# esp32buscam_01.net
KiCad netlist of a schematic drawn in EAGLE
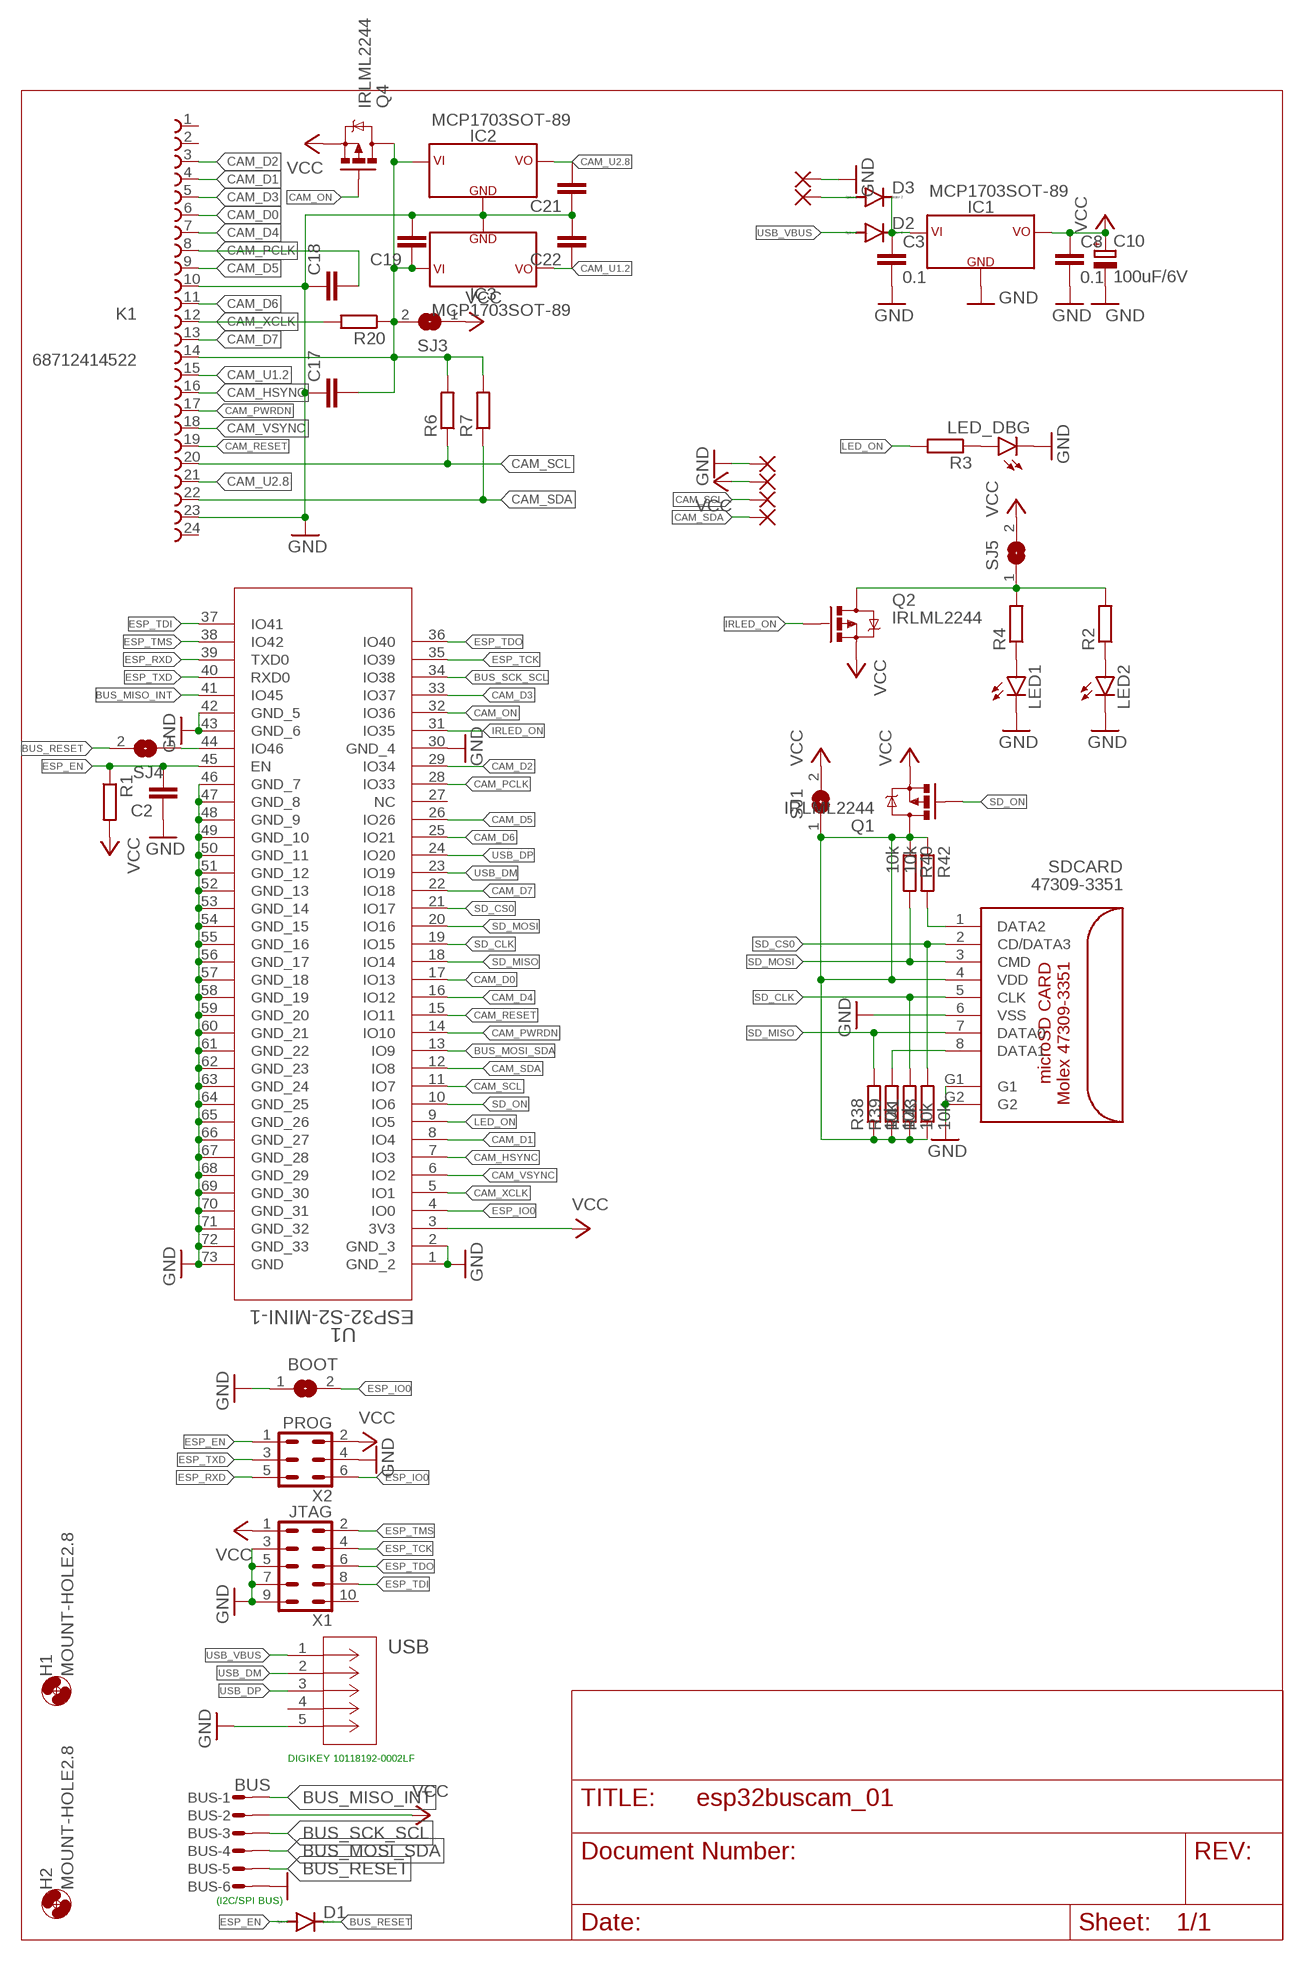
[diagram p0: schematic, sheet 1]

(export (version "E")
  (design (tool "Eeschema 10.0.6"))
  (components
    (comp (ref "BOOT")
      (value "SJ")
      (footprint "eagle-import:SJ")
      (libsource (lib "eagle-import") (part "SJ"))
    )
    (comp (ref "BUS")
      (value "BUS")
      (footprint "eagle-import:MICROMATCH-6SMD")
      (libsource (lib "eagle-import") (part "MICROMATCH-6SMD"))
    )
    (comp (ref "C2")
      (value "C-EUC0603")
      (footprint "eagle-import:C0603")
      (libsource (lib "eagle-import") (part "rcl_334_C-EUC0603"))
    )
    (comp (ref "C3")
      (value "0.1")
      (footprint "eagle-import:C0805")
      (libsource (lib "eagle-import") (part "C-EUC0805"))
    )
    (comp (ref "C8")
      (value "0.1")
      (footprint "eagle-import:C0805")
      (libsource (lib "eagle-import") (part "C-EUC0805"))
    )
    (comp (ref "C10")
      (value "100uF/6V")
      (footprint "eagle-import:B_3528-21R")
      (libsource (lib "eagle-import") (part "CPOL-EUB/3528-21R"))
    )
    (comp (ref "C17")
      (value "C-EUC0603")
      (footprint "eagle-import:C0603")
      (libsource (lib "eagle-import") (part "rcl_334_C-EUC0603"))
    )
    (comp (ref "C18")
      (value "C-EUC0603")
      (footprint "eagle-import:C0603")
      (libsource (lib "eagle-import") (part "rcl_334_C-EUC0603"))
    )
    (comp (ref "C19")
      (value "C-EUC0603")
      (footprint "eagle-import:C0603")
      (libsource (lib "eagle-import") (part "rcl_334_C-EUC0603"))
    )
    (comp (ref "C21")
      (value "C-EUC0603")
      (footprint "eagle-import:C0603")
      (libsource (lib "eagle-import") (part "rcl_334_C-EUC0603"))
    )
    (comp (ref "C22")
      (value "C-EUC0603")
      (footprint "eagle-import:C0603")
      (libsource (lib "eagle-import") (part "rcl_334_C-EUC0603"))
    )
    (comp (ref "D1")
      (value "DIODE-MINIMELF")
      (footprint "eagle-import:MINIMELF")
      (libsource (lib "eagle-import") (part "DIODE-MINIMELF"))
    )
    (comp (ref "D2")
      (value "DIODE-MINIMELF")
      (footprint "eagle-import:MINIMELF")
      (libsource (lib "eagle-import") (part "DIODE-MINIMELF"))
    )
    (comp (ref "D3")
      (value "DIODE-MINIMELF")
      (footprint "eagle-import:MINIMELF")
      (libsource (lib "eagle-import") (part "DIODE-MINIMELF"))
    )
    (comp (ref "H1")
      (value "MOUNT-HOLE2.8")
      (footprint "eagle-import:2,8")
      (libsource (lib "eagle-import") (part "MOUNT-HOLE2.8"))
    )
    (comp (ref "H2")
      (value "MOUNT-HOLE2.8")
      (footprint "eagle-import:2,8")
      (libsource (lib "eagle-import") (part "MOUNT-HOLE2.8"))
    )
    (comp (ref "IC1")
      (value "MCP1703SOT-89")
      (footprint "eagle-import:SOT89")
      (libsource (lib "eagle-import") (part "MCP1703SOT-89"))
    )
    (comp (ref "IC2")
      (value "MCP1703SOT-89")
      (footprint "eagle-import:SOT89")
      (libsource (lib "eagle-import") (part "MCP1703SOT-89"))
    )
    (comp (ref "IC3")
      (value "MCP1703SOT-89")
      (footprint "eagle-import:SOT89")
      (libsource (lib "eagle-import") (part "MCP1703SOT-89"))
    )
    (comp (ref "K1")
      (value "68712414522")
      (footprint "eagle-import:68712414522")
      (libsource (lib "eagle-import") (part "68712414522"))
    )
    (comp (ref "LED1")
      (value "LED5MM")
      (footprint "eagle-import:LED5MM")
      (libsource (lib "eagle-import") (part "LED5MM"))
    )
    (comp (ref "LED2")
      (value "LED5MM")
      (footprint "eagle-import:LED5MM")
      (libsource (lib "eagle-import") (part "LED5MM"))
    )
    (comp (ref "LED_DBG")
      (value "G")
      (footprint "eagle-import:CHIPLED_0805")
      (libsource (lib "eagle-import") (part "LEDCHIPLED_0805"))
    )
    (comp (ref "PAD1")
      (value "1,6/0,9")
      (footprint "eagle-import:1,6_0,9")
      (libsource (lib "eagle-import") (part "1,6/0,9"))
    )
    (comp (ref "PAD2")
      (value "1,6/0,9")
      (footprint "eagle-import:1,6_0,9")
      (libsource (lib "eagle-import") (part "1,6/0,9"))
    )
    (comp (ref "PAD3")
      (value "1,6/0,9")
      (footprint "eagle-import:1,6_0,9")
      (libsource (lib "eagle-import") (part "1,6/0,9"))
    )
    (comp (ref "PAD4")
      (value "1,6/0,9")
      (footprint "eagle-import:1,6_0,9")
      (libsource (lib "eagle-import") (part "1,6/0,9"))
    )
    (comp (ref "PAD5")
      (value "1,6/0,9")
      (footprint "eagle-import:1,6_0,9")
      (libsource (lib "eagle-import") (part "1,6/0,9"))
    )
    (comp (ref "PAD6")
      (value "1,6/0,9")
      (footprint "eagle-import:1,6_0,9")
      (libsource (lib "eagle-import") (part "1,6/0,9"))
    )
    (comp (ref "Q1")
      (value "IRLML2244")
      (footprint "eagle-import:SOT23-3")
      (libsource (lib "eagle-import") (part "MOSFET-PCHANNELIRLML2244"))
    )
    (comp (ref "Q2")
      (value "IRLML2244")
      (footprint "eagle-import:SOT23-3")
      (libsource (lib "eagle-import") (part "MOSFET-PCHANNELIRLML2244"))
    )
    (comp (ref "Q4")
      (value "IRLML2244")
      (footprint "eagle-import:SOT23-3")
      (libsource (lib "eagle-import") (part "MOSFET-PCHANNELIRLML2244"))
    )
    (comp (ref "R1")
      (value "R-EU_R0603")
      (footprint "eagle-import:R0603")
      (libsource (lib "eagle-import") (part "rcl_334_R-EU_R0603"))
    )
    (comp (ref "R2")
      (value "R-EU_R0402")
      (footprint "eagle-import:R0402")
      (libsource (lib "eagle-import") (part "rcl_334_R-EU_R0402"))
    )
    (comp (ref "R3")
      (value "R-EU_R0402")
      (footprint "eagle-import:R0402")
      (libsource (lib "eagle-import") (part "rcl_334_R-EU_R0402"))
    )
    (comp (ref "R4")
      (value "R-EU_R0402")
      (footprint "eagle-import:R0402")
      (libsource (lib "eagle-import") (part "rcl_334_R-EU_R0402"))
    )
    (comp (ref "R6")
      (value "R-EU_R0603")
      (footprint "eagle-import:R0603")
      (libsource (lib "eagle-import") (part "rcl_334_R-EU_R0603"))
    )
    (comp (ref "R7")
      (value "R-EU_R0603")
      (footprint "eagle-import:R0603")
      (libsource (lib "eagle-import") (part "rcl_334_R-EU_R0603"))
    )
    (comp (ref "R20")
      (value "R-EU_R0603")
      (footprint "eagle-import:R0603")
      (libsource (lib "eagle-import") (part "rcl_334_R-EU_R0603"))
    )
    (comp (ref "R38")
      (value "10k")
      (footprint "eagle-import:R0805")
      (libsource (lib "eagle-import") (part "R-EU_R0805"))
    )
    (comp (ref "R39")
      (value "10k")
      (footprint "eagle-import:R0805")
      (libsource (lib "eagle-import") (part "R-EU_R0805"))
    )
    (comp (ref "R40")
      (value "10k")
      (footprint "eagle-import:R0805")
      (libsource (lib "eagle-import") (part "R-EU_R0805"))
    )
    (comp (ref "R41")
      (value "10k")
      (footprint "eagle-import:R0805")
      (libsource (lib "eagle-import") (part "R-EU_R0805"))
    )
    (comp (ref "R42")
      (value "10k")
      (footprint "eagle-import:R0805")
      (libsource (lib "eagle-import") (part "R-EU_R0805"))
    )
    (comp (ref "R43")
      (value "10k")
      (footprint "eagle-import:R0805")
      (libsource (lib "eagle-import") (part "R-EU_R0805"))
    )
    (comp (ref "SDCARD")
      (value "47309-3351")
      (footprint "eagle-import:47309-3351")
      (libsource (lib "eagle-import") (part "47309-3351"))
    )
    (comp (ref "SJ1") (value "SJ") (footprint "eagle-import:SJ") (libsource (lib "eagle-import") (part "SJ")))
    (comp (ref "SJ3") (value "SJ") (footprint "eagle-import:SJ") (libsource (lib "eagle-import") (part "SJ")))
    (comp (ref "SJ4") (value "SJ") (footprint "eagle-import:SJ") (libsource (lib "eagle-import") (part "SJ")))
    (comp (ref "SJ5") (value "SJ") (footprint "eagle-import:SJ") (libsource (lib "eagle-import") (part "SJ")))
    (comp (ref "U1")
      (value "ESP32-S2-MINI-1")
      (footprint "eagle-import:QFN60_ESP32-S2-MINI-1_EXP")
      (fields (field (name "COPYRIGHT") "Copyright (C) 2018 Accelerated Designs. All rights reserved"))
      (libsource (lib "eagle-import") (part "ESP32-S2-MINI-1"))
    )
    (comp (ref "USB")
      (value "10118192-0002LF")
      (footprint "eagle-import:CONN_10118192-0002LF_AMP")
      (fields (field (name "COPYRIGHT") "Copyright (C) 2018 Accelerated Designs. All rights reserved"))
      (libsource (lib "eagle-import") (part "10118192-0002LF"))
    )
    (comp (ref "X1")
      (value "JTAG")
      (footprint "eagle-import:PHB_1MM27_2X05_SNS")
      (libsource (lib "eagle-import") (part "PHB_1MM27_2X05_SNS"))
    )
    (comp (ref "X2")
      (value "PROG")
      (footprint "eagle-import:PHB_1MM27_2X03_SNS")
      (libsource (lib "eagle-import") (part "PHB_1MM27_2X03_SNS"))
    )
  )
  (nets
    (net (code "1") (name "BUS_MISO_INT") (class "Default")
      (node (ref "BUS") (pin "1") (pinfunction "S_1") (pintype "passive"))
      (node (ref "U1") (pin "41") (pinfunction "IO45_41") (pintype "bidirectional"))
    )
    (net (code "2") (name "BUS_MOSI_SDA") (class "Default")
      (node (ref "BUS") (pin "4") (pinfunction "S_4") (pintype "passive"))
      (node (ref "U1") (pin "13") (pinfunction "IO9_13") (pintype "bidirectional"))
    )
    (net (code "3") (name "BUS_RESET") (class "Default")
      (node (ref "BUS") (pin "5") (pinfunction "S_5") (pintype "passive"))
      (node (ref "D1") (pin "C") (pinfunction "C_C") (pintype "passive"))
      (node (ref "SJ4") (pin "2") (pinfunction "2_2") (pintype "passive"))
    )
    (net (code "4") (name "BUS_SCK_SCL") (class "Default")
      (node (ref "BUS") (pin "3") (pinfunction "S_3") (pintype "passive"))
      (node (ref "U1") (pin "34") (pinfunction "IO38_34") (pintype "bidirectional"))
    )
    (net (code "5") (name "CAM_D0") (class "Default")
      (node (ref "K1") (pin "6") (pinfunction "6_6") (pintype "passive"))
      (node (ref "U1") (pin "17") (pinfunction "IO13_17") (pintype "bidirectional"))
    )
    (net (code "6") (name "CAM_D1") (class "Default")
      (node (ref "K1") (pin "4") (pinfunction "4_4") (pintype "passive"))
      (node (ref "U1") (pin "8") (pinfunction "IO4_8") (pintype "bidirectional"))
    )
    (net (code "7") (name "CAM_D2") (class "Default")
      (node (ref "K1") (pin "3") (pinfunction "3_3") (pintype "passive"))
      (node (ref "U1") (pin "29") (pinfunction "IO34_29") (pintype "bidirectional"))
    )
    (net (code "8") (name "CAM_D3") (class "Default")
      (node (ref "K1") (pin "5") (pinfunction "5_5") (pintype "passive"))
      (node (ref "U1") (pin "33") (pinfunction "IO37_33") (pintype "bidirectional"))
    )
    (net (code "9") (name "CAM_D4") (class "Default")
      (node (ref "K1") (pin "7") (pinfunction "7_7") (pintype "passive"))
      (node (ref "U1") (pin "16") (pinfunction "IO12_16") (pintype "bidirectional"))
    )
    (net (code "10") (name "CAM_D5") (class "Default")
      (node (ref "K1") (pin "9") (pinfunction "9_9") (pintype "passive"))
      (node (ref "U1") (pin "26") (pinfunction "IO26_26") (pintype "bidirectional"))
    )
    (net (code "11") (name "CAM_D6") (class "Default")
      (node (ref "K1") (pin "11") (pinfunction "11_11") (pintype "passive"))
      (node (ref "U1") (pin "25") (pinfunction "IO21_25") (pintype "bidirectional"))
    )
    (net (code "12") (name "CAM_D7") (class "Default")
      (node (ref "K1") (pin "13") (pinfunction "13_13") (pintype "passive"))
      (node (ref "U1") (pin "22") (pinfunction "IO18_22") (pintype "bidirectional"))
    )
    (net (code "13") (name "CAM_HSYNC") (class "Default")
      (node (ref "K1") (pin "16") (pinfunction "16_16") (pintype "passive"))
      (node (ref "U1") (pin "7") (pinfunction "IO3_7") (pintype "bidirectional"))
    )
    (net (code "14") (name "CAM_ON") (class "Default")
      (node (ref "Q4") (pin "1") (pinfunction "G_1") (pintype "passive"))
      (node (ref "U1") (pin "32") (pinfunction "IO36_32") (pintype "bidirectional"))
    )
    (net (code "15") (name "CAM_PCLK") (class "Default")
      (node (ref "C18") (pin "2") (pinfunction "2_2") (pintype "passive"))
      (node (ref "K1") (pin "8") (pinfunction "8_8") (pintype "passive"))
      (node (ref "U1") (pin "28") (pinfunction "IO33_28") (pintype "bidirectional"))
    )
    (net (code "16") (name "CAM_PWRDN") (class "Default")
      (node (ref "K1") (pin "17") (pinfunction "17_17") (pintype "passive"))
      (node (ref "U1") (pin "14") (pinfunction "IO10_14") (pintype "bidirectional"))
    )
    (net (code "17") (name "CAM_RESET") (class "Default")
      (node (ref "K1") (pin "19") (pinfunction "19_19") (pintype "passive"))
      (node (ref "U1") (pin "15") (pinfunction "IO11_15") (pintype "bidirectional"))
    )
    (net (code "18") (name "CAM_SCL") (class "Default")
      (node (ref "K1") (pin "20") (pinfunction "20_20") (pintype "passive"))
      (node (ref "PAD3") (pin "1") (pinfunction "P_1") (pintype "passive"))
      (node (ref "R6") (pin "1") (pinfunction "1_1") (pintype "passive"))
      (node (ref "U1") (pin "11") (pinfunction "IO7_11") (pintype "bidirectional"))
    )
    (net (code "19") (name "CAM_SDA") (class "Default")
      (node (ref "K1") (pin "22") (pinfunction "22_22") (pintype "passive"))
      (node (ref "PAD4") (pin "1") (pinfunction "P_1") (pintype "passive"))
      (node (ref "R7") (pin "1") (pinfunction "1_1") (pintype "passive"))
      (node (ref "U1") (pin "12") (pinfunction "IO8_12") (pintype "bidirectional"))
    )
    (net (code "20") (name "CAM_U1.2") (class "Default")
      (node (ref "C22") (pin "1") (pinfunction "1_1") (pintype "passive"))
      (node (ref "IC3") (pin "3") (pinfunction "VCC_3") (pintype "power_in"))
      (node (ref "K1") (pin "15") (pinfunction "15_15") (pintype "passive"))
    )
    (net (code "21") (name "CAM_U2.8") (class "Default")
      (node (ref "C21") (pin "2") (pinfunction "2_2") (pintype "passive"))
      (node (ref "IC2") (pin "3") (pinfunction "VCC_3") (pintype "power_in"))
      (node (ref "K1") (pin "21") (pinfunction "21_21") (pintype "passive"))
    )
    (net (code "22") (name "CAM_VSYNC") (class "Default")
      (node (ref "K1") (pin "18") (pinfunction "18_18") (pintype "passive"))
      (node (ref "U1") (pin "6") (pinfunction "IO2_6") (pintype "bidirectional"))
    )
    (net (code "23") (name "CAM_XCLK") (class "Default")
      (node (ref "K1") (pin "12") (pinfunction "12_12") (pintype "passive"))
      (node (ref "R20") (pin "2") (pinfunction "2_2") (pintype "passive"))
      (node (ref "U1") (pin "5") (pinfunction "IO1_5") (pintype "bidirectional"))
    )
    (net (code "24") (name "ESP_EN") (class "Default")
      (node (ref "C2") (pin "2") (pinfunction "2_2") (pintype "passive"))
      (node (ref "D1") (pin "A") (pinfunction "A_A") (pintype "passive"))
      (node (ref "R1") (pin "1") (pinfunction "1_1") (pintype "passive"))
      (node (ref "U1") (pin "45") (pinfunction "EN_45") (pintype "passive"))
      (node (ref "X2") (pin "1") (pinfunction "1_1") (pintype "passive"))
    )
    (net (code "25") (name "ESP_IO0") (class "Default")
      (node (ref "BOOT") (pin "2") (pinfunction "2_2") (pintype "passive"))
      (node (ref "U1") (pin "4") (pinfunction "IO0_4") (pintype "bidirectional"))
      (node (ref "X2") (pin "6") (pinfunction "6_6") (pintype "passive"))
    )
    (net (code "26") (name "ESP_RXD") (class "Default")
      (node (ref "U1") (pin "39") (pinfunction "TXD0_39") (pintype "bidirectional"))
      (node (ref "X2") (pin "5") (pinfunction "5_5") (pintype "passive"))
    )
    (net (code "27") (name "ESP_TCK") (class "Default")
      (node (ref "U1") (pin "35") (pinfunction "IO39_35") (pintype "bidirectional"))
      (node (ref "X1") (pin "4") (pinfunction "4_4") (pintype "passive"))
    )
    (net (code "28") (name "ESP_TDI") (class "Default")
      (node (ref "U1") (pin "37") (pinfunction "IO41_37") (pintype "bidirectional"))
      (node (ref "X1") (pin "8") (pinfunction "8_8") (pintype "passive"))
    )
    (net (code "29") (name "ESP_TDO") (class "Default")
      (node (ref "U1") (pin "36") (pinfunction "IO40_36") (pintype "bidirectional"))
      (node (ref "X1") (pin "6") (pinfunction "6_6") (pintype "passive"))
    )
    (net (code "30") (name "ESP_TMS") (class "Default")
      (node (ref "U1") (pin "38") (pinfunction "IO42_38") (pintype "bidirectional"))
      (node (ref "X1") (pin "2") (pinfunction "2_2") (pintype "passive"))
    )
    (net (code "31") (name "ESP_TXD") (class "Default")
      (node (ref "U1") (pin "40") (pinfunction "RXD0_40") (pintype "bidirectional"))
      (node (ref "X2") (pin "3") (pinfunction "3_3") (pintype "passive"))
    )
    (net (code "32") (name "GND") (class "Default")
      (node (ref "BOOT") (pin "1") (pinfunction "1_1") (pintype "passive"))
      (node (ref "BUS") (pin "6") (pinfunction "S_6") (pintype "passive"))
      (node (ref "C10") (pin "-") (pinfunction "-_-") (pintype "passive"))
      (node (ref "C17") (pin "1") (pinfunction "1_1") (pintype "passive"))
      (node (ref "C18") (pin "1") (pinfunction "1_1") (pintype "passive"))
      (node (ref "C19") (pin "2") (pinfunction "2_2") (pintype "passive"))
      (node (ref "C2") (pin "1") (pinfunction "1_1") (pintype "passive"))
      (node (ref "C21") (pin "1") (pinfunction "1_1") (pintype "passive"))
      (node (ref "C22") (pin "2") (pinfunction "2_2") (pintype "passive"))
      (node (ref "C3") (pin "2") (pinfunction "2_2") (pintype "passive"))
      (node (ref "C8") (pin "2") (pinfunction "2_2") (pintype "passive"))
      (node (ref "IC1") (pin "1") (pinfunction "GND_1") (pintype "power_in"))
      (node (ref "IC2") (pin "1") (pinfunction "GND_1") (pintype "power_in"))
      (node (ref "IC3") (pin "1") (pinfunction "GND_1") (pintype "power_in"))
      (node (ref "K1") (pin "10") (pinfunction "10_10") (pintype "passive"))
      (node (ref "K1") (pin "23") (pinfunction "23_23") (pintype "passive"))
      (node (ref "LED1") (pin "K") (pinfunction "C_K") (pintype "passive"))
      (node (ref "LED2") (pin "K") (pinfunction "C_K") (pintype "passive"))
      (node (ref "LED_DBG") (pin "C") (pinfunction "C_C") (pintype "passive"))
      (node (ref "PAD1") (pin "1") (pinfunction "P_1") (pintype "passive"))
      (node (ref "PAD6") (pin "1") (pinfunction "P_1") (pintype "passive"))
      (node (ref "SDCARD") (pin "6") (pinfunction "VSS_6") (pintype "bidirectional"))
      (node (ref "SDCARD") (pin "G1") (pinfunction "G1_G1") (pintype "bidirectional"))
      (node (ref "SDCARD") (pin "G2") (pinfunction "G2_G2") (pintype "bidirectional"))
      (node (ref "U1") (pin "1") (pinfunction "GND_2_1") (pintype "passive"))
      (node (ref "U1") (pin "2") (pinfunction "GND_3_2") (pintype "passive"))
      (node (ref "U1") (pin "30") (pinfunction "GND_4_30") (pintype "passive"))
      (node (ref "U1") (pin "42") (pinfunction "GND_5_42") (pintype "passive"))
      (node (ref "U1") (pin "43") (pinfunction "GND_6_43") (pintype "passive"))
      (node (ref "U1") (pin "46") (pinfunction "GND_7_46") (pintype "passive"))
      (node (ref "U1") (pin "47") (pinfunction "GND_8_47") (pintype "passive"))
      (node (ref "U1") (pin "48") (pinfunction "GND_9_48") (pintype "passive"))
      (node (ref "U1") (pin "49") (pinfunction "GND_10_49") (pintype "passive"))
      (node (ref "U1") (pin "50") (pinfunction "GND_11_50") (pintype "passive"))
      (node (ref "U1") (pin "51") (pinfunction "GND_12_51") (pintype "passive"))
      (node (ref "U1") (pin "52") (pinfunction "GND_13_52") (pintype "passive"))
      (node (ref "U1") (pin "53") (pinfunction "GND_14_53") (pintype "passive"))
      (node (ref "U1") (pin "54") (pinfunction "GND_15_54") (pintype "passive"))
      (node (ref "U1") (pin "55") (pinfunction "GND_16_55") (pintype "passive"))
      (node (ref "U1") (pin "56") (pinfunction "GND_17_56") (pintype "passive"))
      (node (ref "U1") (pin "57") (pinfunction "GND_18_57") (pintype "passive"))
      (node (ref "U1") (pin "58") (pinfunction "GND_19_58") (pintype "passive"))
      (node (ref "U1") (pin "59") (pinfunction "GND_20_59") (pintype "passive"))
      (node (ref "U1") (pin "60") (pinfunction "GND_21_60") (pintype "passive"))
      (node (ref "U1") (pin "61") (pinfunction "GND_22_61") (pintype "passive"))
      (node (ref "U1") (pin "62") (pinfunction "GND_23_62") (pintype "passive"))
      (node (ref "U1") (pin "63") (pinfunction "GND_24_63") (pintype "passive"))
      (node (ref "U1") (pin "64") (pinfunction "GND_25_64") (pintype "passive"))
      (node (ref "U1") (pin "65") (pinfunction "GND_26_65") (pintype "passive"))
      (node (ref "U1") (pin "66") (pinfunction "GND_27_66") (pintype "passive"))
      (node (ref "U1") (pin "67") (pinfunction "GND_28_67") (pintype "passive"))
      (node (ref "U1") (pin "68") (pinfunction "GND_29_68") (pintype "passive"))
      (node (ref "U1") (pin "69") (pinfunction "GND_30_69") (pintype "passive"))
      (node (ref "U1") (pin "70") (pinfunction "GND_31_70") (pintype "passive"))
      (node (ref "U1") (pin "71") (pinfunction "GND_32_71") (pintype "passive"))
      (node (ref "U1") (pin "72") (pinfunction "GND_33_72") (pintype "passive"))
      (node (ref "U1") (pin "73") (pinfunction "GND_73") (pintype "passive"))
      (node (ref "USB") (pin "5") (pinfunction "5_5") (pintype "passive"))
      (node (ref "X1") (pin "3") (pinfunction "3_3") (pintype "passive"))
      (node (ref "X1") (pin "5") (pinfunction "5_5") (pintype "passive"))
      (node (ref "X1") (pin "7") (pinfunction "7_7") (pintype "passive"))
      (node (ref "X1") (pin "9") (pinfunction "9_9") (pintype "passive"))
      (node (ref "X2") (pin "4") (pinfunction "4_4") (pintype "passive"))
    )
    (net (code "33") (name "IRLED_ON") (class "Default")
      (node (ref "Q2") (pin "1") (pinfunction "G_1") (pintype "passive"))
      (node (ref "U1") (pin "31") (pinfunction "IO35_31") (pintype "bidirectional"))
    )
    (net (code "34") (name "LED_ON") (class "Default")
      (node (ref "R3") (pin "2") (pinfunction "2_2") (pintype "passive"))
      (node (ref "U1") (pin "9") (pinfunction "IO5_9") (pintype "bidirectional"))
    )
    (net (code "35") (name "Net-(C3-Pad1)") (class "Default")
      (node (ref "C3") (pin "1") (pinfunction "1_1") (pintype "passive"))
      (node (ref "D2") (pin "C") (pinfunction "C_C") (pintype "passive"))
      (node (ref "D3") (pin "C") (pinfunction "C_C") (pintype "passive"))
      (node (ref "IC1") (pin "2") (pinfunction "VIN_2") (pintype "power_in"))
      (node (ref "IC1") (pin "4") (pinfunction "VIN_4") (pintype "power_in"))
    )
    (net (code "36") (name "Net-(LED1-PadA)") (class "Default")
      (node (ref "LED1") (pin "A") (pinfunction "A_A") (pintype "passive"))
      (node (ref "R4") (pin "1") (pinfunction "1_1") (pintype "passive"))
    )
    (net (code "37") (name "Net-(LED2-PadA)") (class "Default")
      (node (ref "LED2") (pin "A") (pinfunction "A_A") (pintype "passive"))
      (node (ref "R2") (pin "1") (pinfunction "1_1") (pintype "passive"))
    )
    (net (code "38") (name "Net-(LED_DBG-PadA)") (class "Default")
      (node (ref "LED_DBG") (pin "A") (pinfunction "A_A") (pintype "passive"))
      (node (ref "R3") (pin "1") (pinfunction "1_1") (pintype "passive"))
    )
    (net (code "39") (name "Net-(PAD5-P)") (class "Default")
      (node (ref "D3") (pin "A") (pinfunction "A_A") (pintype "passive"))
      (node (ref "PAD5") (pin "1") (pinfunction "P_1") (pintype "passive"))
    )
    (net (code "40") (name "Net-(Q1-D)") (class "Default")
      (node (ref "Q1") (pin "3") (pinfunction "D_3") (pintype "passive"))
      (node (ref "R38") (pin "1") (pinfunction "1_1") (pintype "passive"))
      (node (ref "R39") (pin "1") (pinfunction "1_1") (pintype "passive"))
      (node (ref "R40") (pin "1") (pinfunction "1_1") (pintype "passive"))
      (node (ref "R41") (pin "1") (pinfunction "1_1") (pintype "passive"))
      (node (ref "R42") (pin "1") (pinfunction "1_1") (pintype "passive"))
      (node (ref "R43") (pin "1") (pinfunction "1_1") (pintype "passive"))
      (node (ref "SDCARD") (pin "4") (pinfunction "VDD_4") (pintype "bidirectional"))
      (node (ref "SJ1") (pin "1") (pinfunction "1_1") (pintype "passive"))
    )
    (net (code "41") (name "Net-(Q2-D)") (class "Default")
      (node (ref "Q2") (pin "3") (pinfunction "D_3") (pintype "passive"))
      (node (ref "R2") (pin "2") (pinfunction "2_2") (pintype "passive"))
      (node (ref "R4") (pin "2") (pinfunction "2_2") (pintype "passive"))
      (node (ref "SJ5") (pin "1") (pinfunction "1_1") (pintype "passive"))
    )
    (net (code "42") (name "Net-(Q4-D)") (class "Default")
      (node (ref "C17") (pin "2") (pinfunction "2_2") (pintype "passive"))
      (node (ref "C19") (pin "1") (pinfunction "1_1") (pintype "passive"))
      (node (ref "IC2") (pin "2") (pinfunction "VIN_2") (pintype "power_in"))
      (node (ref "IC2") (pin "4") (pinfunction "VIN_4") (pintype "power_in"))
      (node (ref "IC3") (pin "2") (pinfunction "VIN_2") (pintype "power_in"))
      (node (ref "IC3") (pin "4") (pinfunction "VIN_4") (pintype "power_in"))
      (node (ref "K1") (pin "14") (pinfunction "14_14") (pintype "passive"))
      (node (ref "Q4") (pin "3") (pinfunction "D_3") (pintype "passive"))
      (node (ref "R20") (pin "1") (pinfunction "1_1") (pintype "passive"))
      (node (ref "R6") (pin "2") (pinfunction "2_2") (pintype "passive"))
      (node (ref "R7") (pin "2") (pinfunction "2_2") (pintype "passive"))
      (node (ref "SJ3") (pin "2") (pinfunction "2_2") (pintype "passive"))
    )
    (net (code "43") (name "Net-(SDCARD-DATA1)") (class "Default")
      (node (ref "R39") (pin "2") (pinfunction "2_2") (pintype "passive"))
      (node (ref "SDCARD") (pin "8") (pinfunction "DATA1_8") (pintype "bidirectional"))
    )
    (net (code "44") (name "Net-(SDCARD-DATA2)") (class "Default")
      (node (ref "R42") (pin "2") (pinfunction "2_2") (pintype "passive"))
      (node (ref "SDCARD") (pin "1") (pinfunction "DATA2_1") (pintype "bidirectional"))
    )
    (net (code "45") (name "Net-(U1-IO46)") (class "Default")
      (node (ref "SJ4") (pin "1") (pinfunction "1_1") (pintype "passive"))
      (node (ref "U1") (pin "44") (pinfunction "IO46_44") (pintype "bidirectional"))
    )
    (net (code "46") (name "SD_CLK") (class "Default")
      (node (ref "R41") (pin "2") (pinfunction "2_2") (pintype "passive"))
      (node (ref "SDCARD") (pin "5") (pinfunction "CLK_5") (pintype "bidirectional"))
      (node (ref "U1") (pin "19") (pinfunction "IO15_19") (pintype "bidirectional"))
    )
    (net (code "47") (name "SD_CS0") (class "Default")
      (node (ref "R43") (pin "2") (pinfunction "2_2") (pintype "passive"))
      (node (ref "SDCARD") (pin "2") (pinfunction "CD/DATA3_2") (pintype "bidirectional"))
      (node (ref "U1") (pin "21") (pinfunction "IO17_21") (pintype "bidirectional"))
    )
    (net (code "48") (name "SD_MISO") (class "Default")
      (node (ref "R38") (pin "2") (pinfunction "2_2") (pintype "passive"))
      (node (ref "SDCARD") (pin "7") (pinfunction "DATA0_7") (pintype "bidirectional"))
      (node (ref "U1") (pin "18") (pinfunction "IO14_18") (pintype "bidirectional"))
    )
    (net (code "49") (name "SD_MOSI") (class "Default")
      (node (ref "R40") (pin "2") (pinfunction "2_2") (pintype "passive"))
      (node (ref "SDCARD") (pin "3") (pinfunction "CMD_3") (pintype "bidirectional"))
      (node (ref "U1") (pin "20") (pinfunction "IO16_20") (pintype "bidirectional"))
    )
    (net (code "50") (name "SD_ON") (class "Default")
      (node (ref "Q1") (pin "1") (pinfunction "G_1") (pintype "passive"))
      (node (ref "U1") (pin "10") (pinfunction "IO6_10") (pintype "bidirectional"))
    )
    (net (code "51") (name "USB_DM") (class "Default")
      (node (ref "U1") (pin "23") (pinfunction "IO19_23") (pintype "bidirectional"))
      (node (ref "USB") (pin "2") (pinfunction "2_2") (pintype "passive"))
    )
    (net (code "52") (name "USB_DP") (class "Default")
      (node (ref "U1") (pin "24") (pinfunction "IO20_24") (pintype "bidirectional"))
      (node (ref "USB") (pin "3") (pinfunction "3_3") (pintype "passive"))
    )
    (net (code "53") (name "USB_VBUS") (class "Default")
      (node (ref "D2") (pin "A") (pinfunction "A_A") (pintype "passive"))
      (node (ref "USB") (pin "1") (pinfunction "1_1") (pintype "passive"))
    )
    (net (code "54") (name "VCC") (class "Default")
      (node (ref "BUS") (pin "2") (pinfunction "S_2") (pintype "passive"))
      (node (ref "C10") (pin "+") (pinfunction "+_+") (pintype "passive"))
      (node (ref "C8") (pin "1") (pinfunction "1_1") (pintype "passive"))
      (node (ref "IC1") (pin "3") (pinfunction "VCC_3") (pintype "power_in"))
      (node (ref "PAD2") (pin "1") (pinfunction "P_1") (pintype "passive"))
      (node (ref "Q1") (pin "2") (pinfunction "S_2") (pintype "passive"))
      (node (ref "Q2") (pin "2") (pinfunction "S_2") (pintype "passive"))
      (node (ref "Q4") (pin "2") (pinfunction "S_2") (pintype "passive"))
      (node (ref "R1") (pin "2") (pinfunction "2_2") (pintype "passive"))
      (node (ref "SJ1") (pin "2") (pinfunction "2_2") (pintype "passive"))
      (node (ref "SJ3") (pin "1") (pinfunction "1_1") (pintype "passive"))
      (node (ref "SJ5") (pin "2") (pinfunction "2_2") (pintype "passive"))
      (node (ref "U1") (pin "3") (pinfunction "3V3_3") (pintype "passive"))
      (node (ref "X1") (pin "1") (pinfunction "1_1") (pintype "passive"))
      (node (ref "X2") (pin "2") (pinfunction "2_2") (pintype "passive"))
    )
    (net (code "55") (name "unconnected-(K1-Pad1)") (class "Default")
      (node (ref "K1") (pin "1") (pinfunction "1_1") (pintype "passive"))
    )
    (net (code "56") (name "unconnected-(K1-Pad2)") (class "Default")
      (node (ref "K1") (pin "2") (pinfunction "2_2") (pintype "passive"))
    )
    (net (code "57") (name "unconnected-(K1-Pad24)") (class "Default")
      (node (ref "K1") (pin "24") (pinfunction "24_24") (pintype "passive"))
    )
    (net (code "58") (name "unconnected-(U1-NC-Pad27)") (class "Default")
      (node (ref "U1") (pin "27") (pinfunction "NC_27") (pintype "no_connect"))
    )
    (net (code "59") (name "unconnected-(USB-Pad4)") (class "Default")
      (node (ref "USB") (pin "4") (pinfunction "4_4") (pintype "passive"))
    )
    (net (code "60") (name "unconnected-(X1-Pad10)") (class "Default")
      (node (ref "X1") (pin "10") (pinfunction "10_10") (pintype "passive"))
    )
  )
)
